# Tag_Schematic.net
KiCad netlist of a schematic drawn in Altium Designer
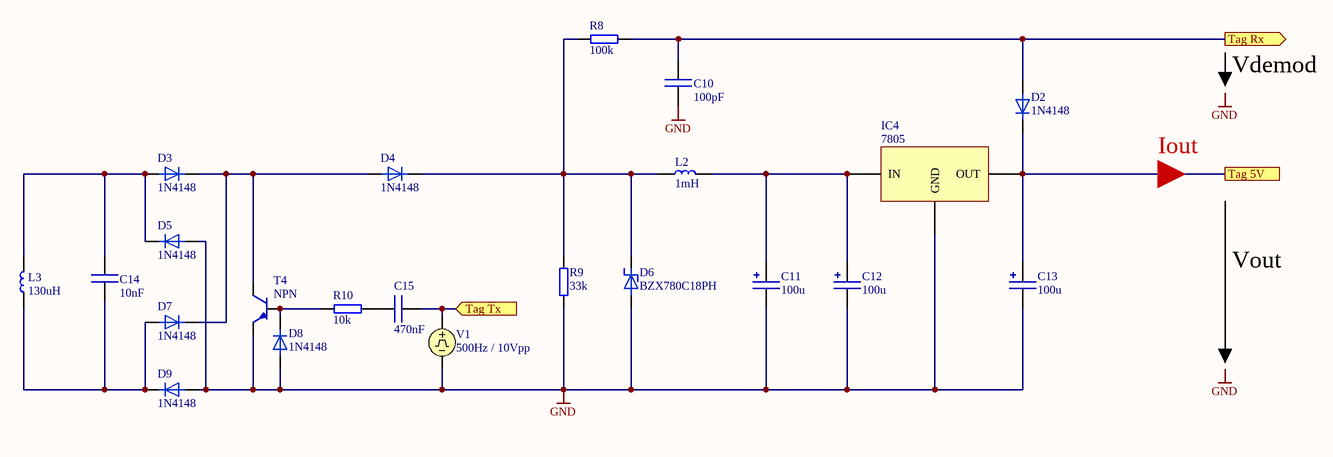
[diagram p0: Tag_Schematic.SchDoc]

(export (version "E")
  (design (tool "Eeschema 10.0.6"))
  (components
    (comp (ref "C10") (value "100pF") (footprint "0805") (libsource (lib "Staudi_Lib") (part "Cap")))
    (comp (ref "C11") (value "100u") (footprint "ELKO_10_5.0") (libsource (lib "Staudi_Lib") (part "Elko")))
    (comp (ref "C12") (value "100u") (footprint "ELKO_10_5.0") (libsource (lib "Staudi_Lib") (part "Elko")))
    (comp (ref "C13") (value "100u") (footprint "ELKO_10_5.0") (libsource (lib "Staudi_Lib") (part "Elko")))
    (comp (ref "C14") (value "10nF") (footprint "0805") (libsource (lib "Staudi_Lib") (part "Cap")))
    (comp (ref "C15") (value "470nF") (footprint "0805") (libsource (lib "Staudi_Lib") (part "Cap")))
    (comp (ref "D2") (value "1N4148") (libsource (lib "Staudi_Lib") (part "Diode")))
    (comp (ref "D3") (value "1N4148") (libsource (lib "Staudi_Lib") (part "Diode")))
    (comp (ref "D4") (value "1N4148") (libsource (lib "Staudi_Lib") (part "Diode")))
    (comp (ref "D5") (value "1N4148") (libsource (lib "Staudi_Lib") (part "Diode")))
    (comp (ref "D6") (value "BZX780C18PH") (libsource (lib "Staudi_Lib") (part "Z-Diode")))
    (comp (ref "D7") (value "1N4148") (libsource (lib "Staudi_Lib") (part "Diode")))
    (comp (ref "D8") (value "1N4148") (libsource (lib "Staudi_Lib") (part "Diode")))
    (comp (ref "D9") (value "1N4148") (libsource (lib "Staudi_Lib") (part "Diode")))
    (comp (ref "IC4")
      (value "7805")
      (description "5V Voltage regulator")
      (libsource (lib "Staudi_Lib") (part "7805"))
    )
    (comp (ref "L2") (value "1mH") (description "Inductor") (libsource (lib "Staudi_Lib") (part "Inductor")))
    (comp (ref "L3") (value "130uH") (description "Inductor") (libsource (lib "") (part "Inductor_1")))
    (comp (ref "R8") (value "100k") (footprint "Axial-04") (libsource (lib "Staudi_Lib") (part "Res")))
    (comp (ref "R9") (value "33k") (footprint "Axial-04") (libsource (lib "Staudi_Lib") (part "Res")))
    (comp (ref "R10") (value "10k") (footprint "Axial-04") (libsource (lib "Staudi_Lib") (part "Res")))
    (comp (ref "T4") (value "NPN") (footprint "2SC3324") (libsource (lib "Staudi_Lib") (part "NPN")))
    (comp (ref "V1")
      (value "500Hz / 10Vpp")
      (description "Pulse Voltage Source")
      (fields (field (name "PUBLISHER") "Altium Limited"))
      (libsource (lib "Simulation Sources") (part "VPULSE"))
    )
  )
  (nets
    (net (code "1") (name "/Tag 5V") (class "Default")
      (node (ref "C13") (pin "1") (pinfunction "1_1") (pintype "passive"))
      (node (ref "D2") (pin "2") (pinfunction "Kathode_2") (pintype "passive"))
      (node (ref "IC4") (pin "2") (pinfunction "OUT_2") (pintype "passive"))
    )
    (net (code "2") (name "/Tag Rx") (class "Default")
      (node (ref "C10") (pin "2") (pinfunction "2_2") (pintype "passive"))
      (node (ref "D2") (pin "1") (pinfunction "Anode_1") (pintype "passive"))
      (node (ref "R8") (pin "2") (pinfunction "2_2") (pintype "passive"))
    )
    (net (code "3") (name "/Tag Tx") (class "Default")
      (node (ref "C15") (pin "2") (pinfunction "2_2") (pintype "passive"))
      (node (ref "V1") (pin "1") (pinfunction "1_1") (pintype "passive"))
    )
    (net (code "4") (name "GND") (class "Default")
      (node (ref "C10") (pin "1") (pinfunction "1_1") (pintype "passive"))
      (node (ref "C11") (pin "2") (pinfunction "2_2") (pintype "passive"))
      (node (ref "C12") (pin "2") (pinfunction "2_2") (pintype "passive"))
      (node (ref "C13") (pin "2") (pinfunction "2_2") (pintype "passive"))
      (node (ref "D5") (pin "1") (pinfunction "Anode_1") (pintype "passive"))
      (node (ref "D6") (pin "1") (pinfunction "Anode_1") (pintype "passive"))
      (node (ref "D8") (pin "1") (pinfunction "Anode_1") (pintype "passive"))
      (node (ref "D9") (pin "1") (pinfunction "Anode_1") (pintype "passive"))
      (node (ref "IC4") (pin "3") (pinfunction "GND_3") (pintype "passive"))
      (node (ref "R9") (pin "1") (pinfunction "1_1") (pintype "passive"))
      (node (ref "T4") (pin "2") (pinfunction "Emitter_2") (pintype "passive"))
      (node (ref "V1") (pin "2") (pinfunction "2_2") (pintype "passive"))
    )
    (net (code "5") (name "Net-(C15-Pad1)") (class "Default")
      (node (ref "C15") (pin "1") (pinfunction "1_1") (pintype "passive"))
      (node (ref "R10") (pin "2") (pinfunction "2_2") (pintype "passive"))
    )
    (net (code "6") (name "Net-(D3-Anode)") (class "Default")
      (node (ref "C14") (pin "2") (pinfunction "2_2") (pintype "passive"))
      (node (ref "D3") (pin "1") (pinfunction "Anode_1") (pintype "passive"))
      (node (ref "D5") (pin "2") (pinfunction "Kathode_2") (pintype "passive"))
      (node (ref "L3") (pin "1") (pinfunction "1_1") (pintype "passive"))
    )
    (net (code "7") (name "Net-(D3-Kathode)") (class "Default")
      (node (ref "D3") (pin "2") (pinfunction "Kathode_2") (pintype "passive"))
      (node (ref "D4") (pin "1") (pinfunction "Anode_1") (pintype "passive"))
      (node (ref "D7") (pin "2") (pinfunction "Kathode_2") (pintype "passive"))
      (node (ref "T4") (pin "3") (pinfunction "Collector_3") (pintype "passive"))
    )
    (net (code "8") (name "Net-(D4-Kathode)") (class "Default")
      (node (ref "D4") (pin "2") (pinfunction "Kathode_2") (pintype "passive"))
      (node (ref "D6") (pin "2") (pinfunction "Kathode_2") (pintype "passive"))
      (node (ref "L2") (pin "2") (pinfunction "2_2") (pintype "passive"))
      (node (ref "R8") (pin "1") (pinfunction "1_1") (pintype "passive"))
      (node (ref "R9") (pin "2") (pinfunction "2_2") (pintype "passive"))
    )
    (net (code "9") (name "Net-(D7-Anode)") (class "Default")
      (node (ref "C14") (pin "1") (pinfunction "1_1") (pintype "passive"))
      (node (ref "D7") (pin "1") (pinfunction "Anode_1") (pintype "passive"))
      (node (ref "D9") (pin "2") (pinfunction "Kathode_2") (pintype "passive"))
      (node (ref "L3") (pin "2") (pinfunction "2_2") (pintype "passive"))
    )
    (net (code "10") (name "Net-(D8-Kathode)") (class "Default")
      (node (ref "D8") (pin "2") (pinfunction "Kathode_2") (pintype "passive"))
      (node (ref "R10") (pin "1") (pinfunction "1_1") (pintype "passive"))
      (node (ref "T4") (pin "1") (pinfunction "Base_1") (pintype "passive"))
    )
    (net (code "11") (name "Net-(IC4-IN)") (class "Default")
      (node (ref "C11") (pin "1") (pinfunction "1_1") (pintype "passive"))
      (node (ref "C12") (pin "1") (pinfunction "1_1") (pintype "passive"))
      (node (ref "IC4") (pin "1") (pinfunction "IN_1") (pintype "passive"))
      (node (ref "L2") (pin "1") (pinfunction "1_1") (pintype "passive"))
    )
  )
)
